# hail.net
KiCad netlist of a schematic drawn in EAGLE
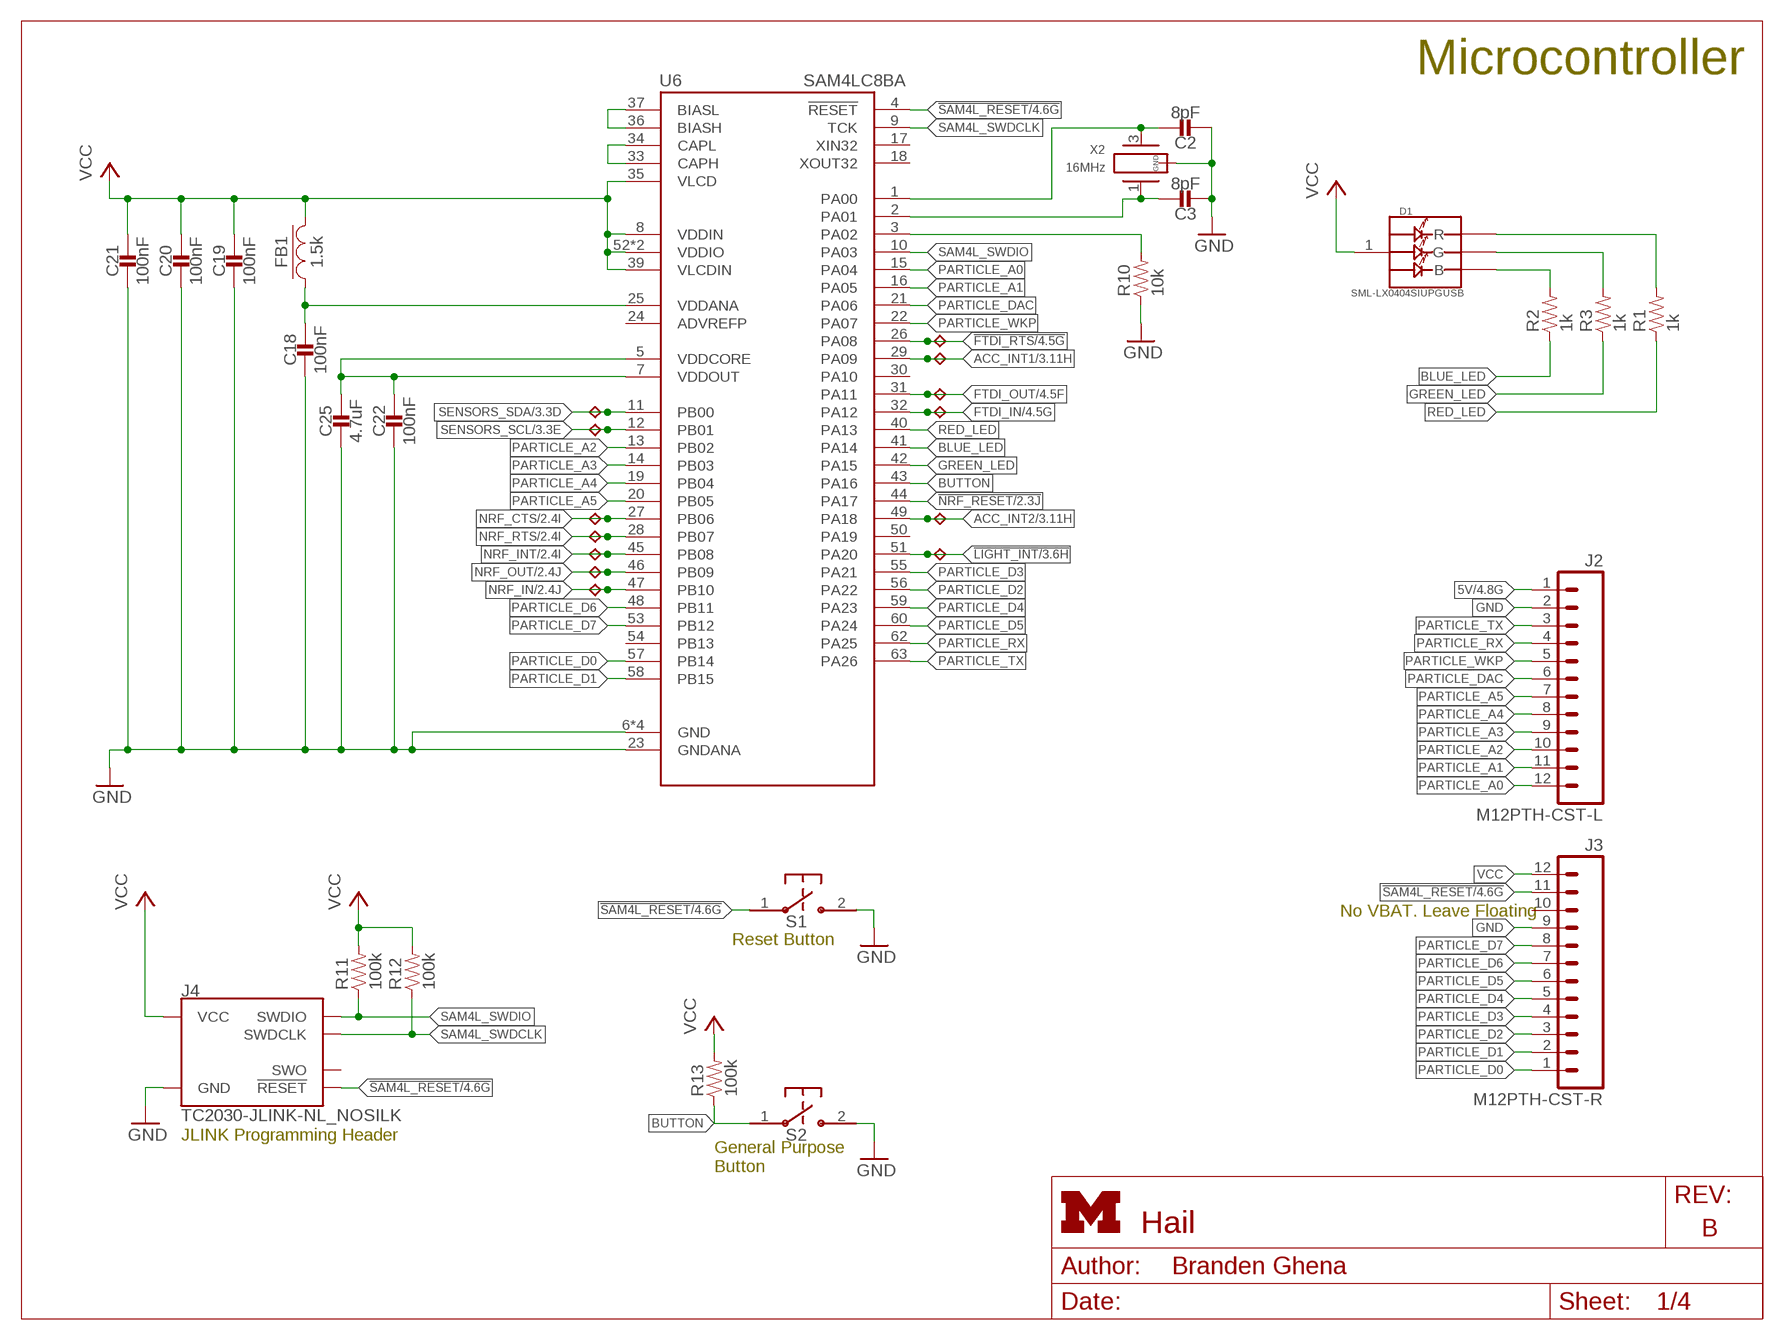
[diagram p0: schematic, sheet 1]
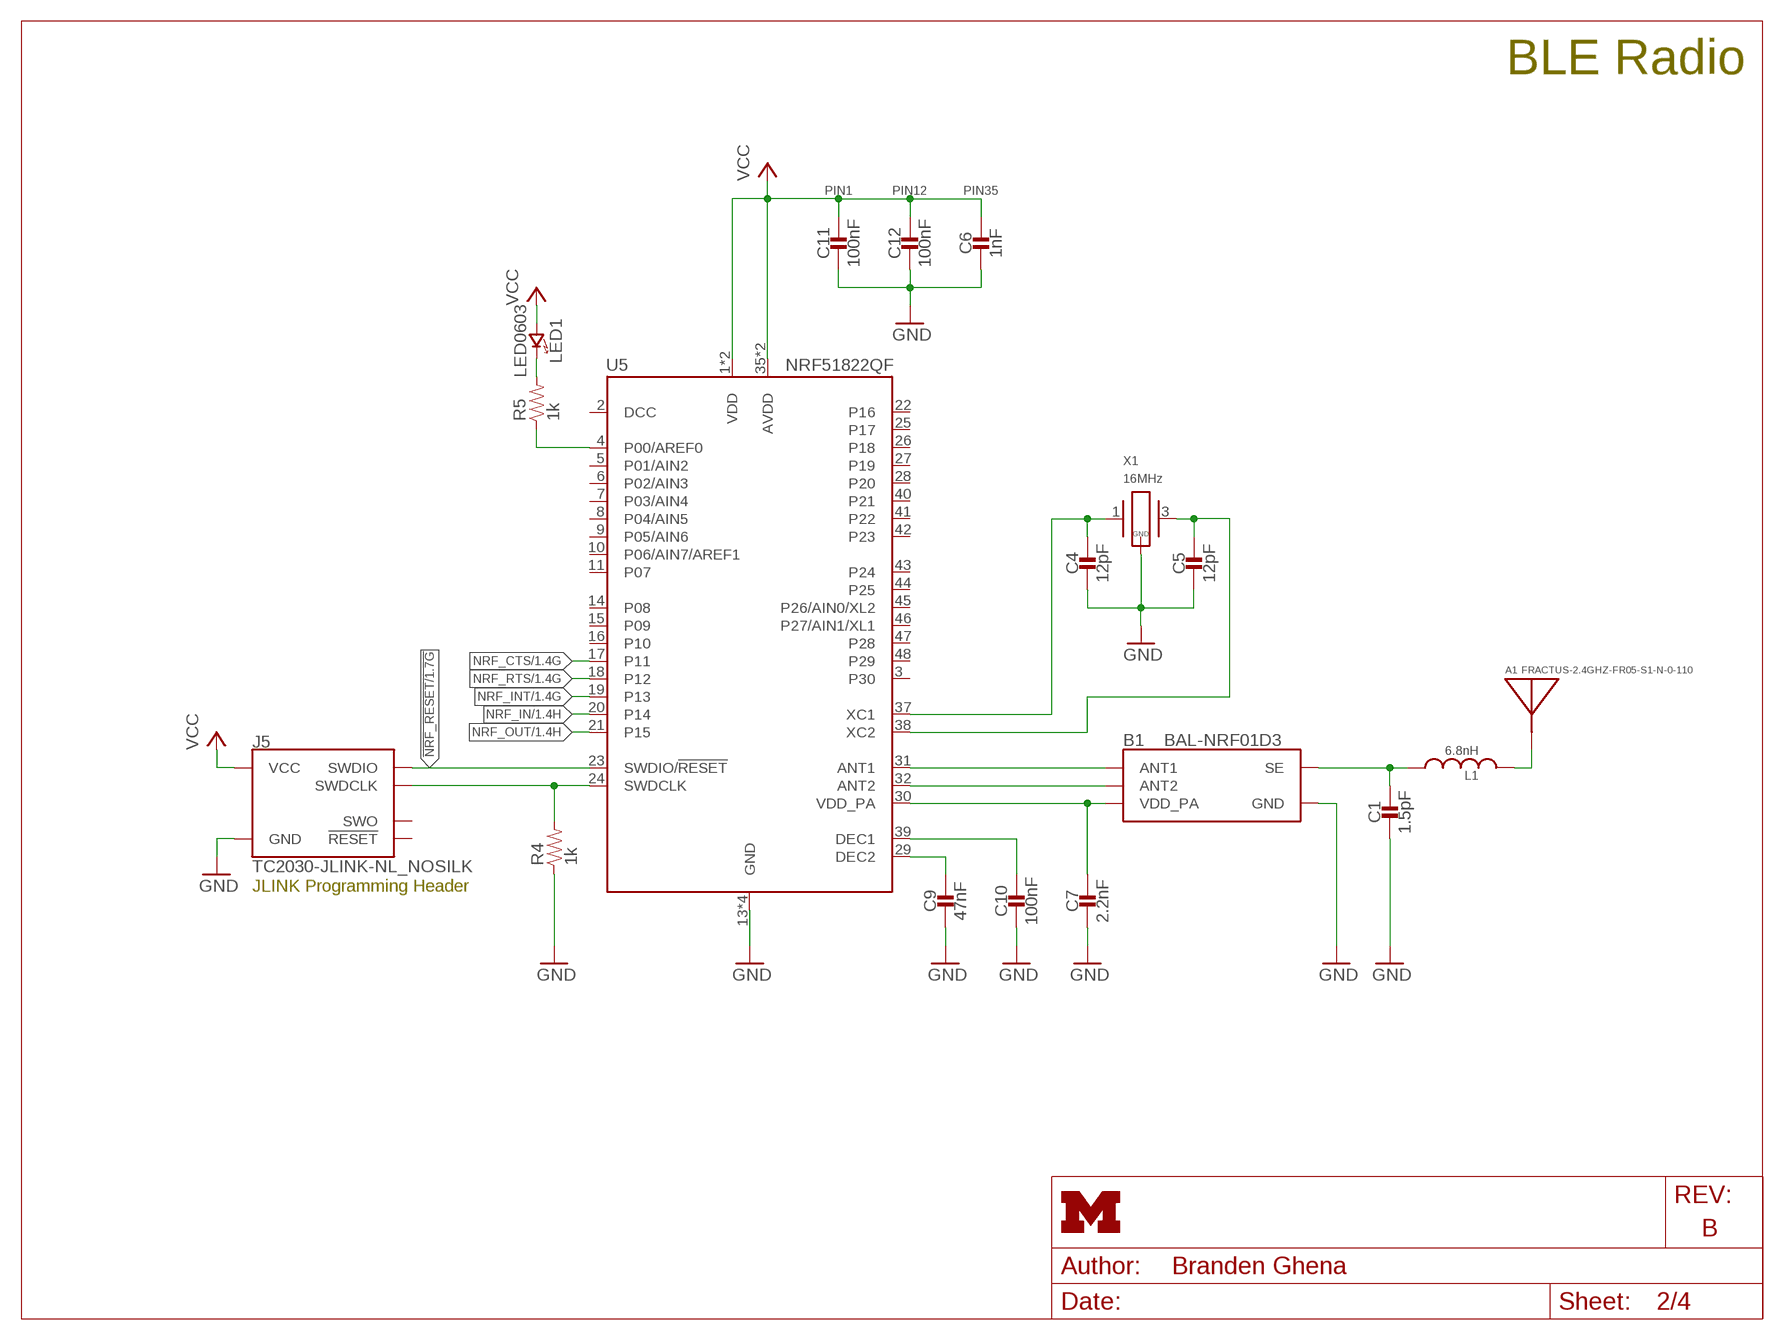
[diagram p1: schematic, sheet 2]
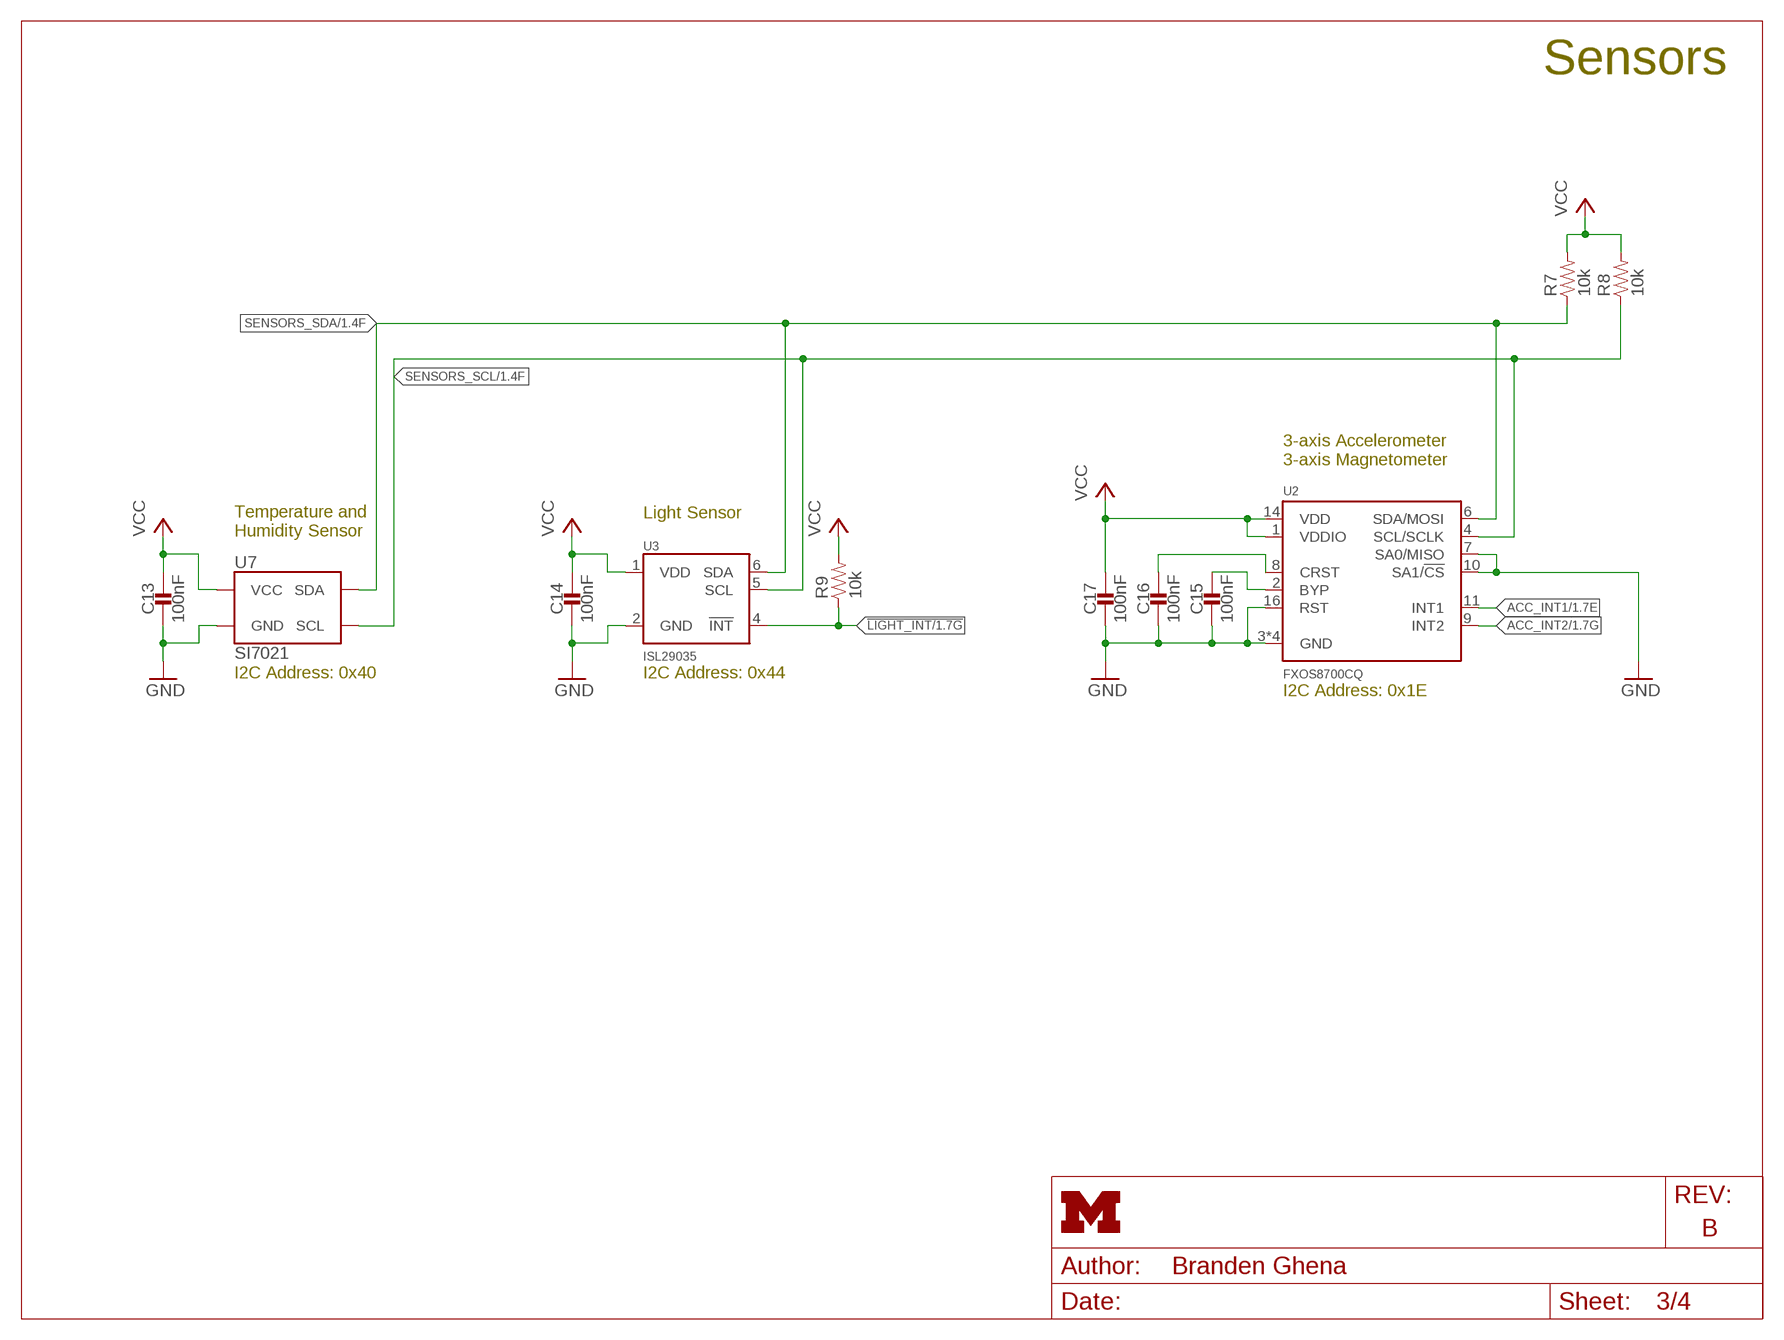
[diagram p2: schematic, sheet 3]
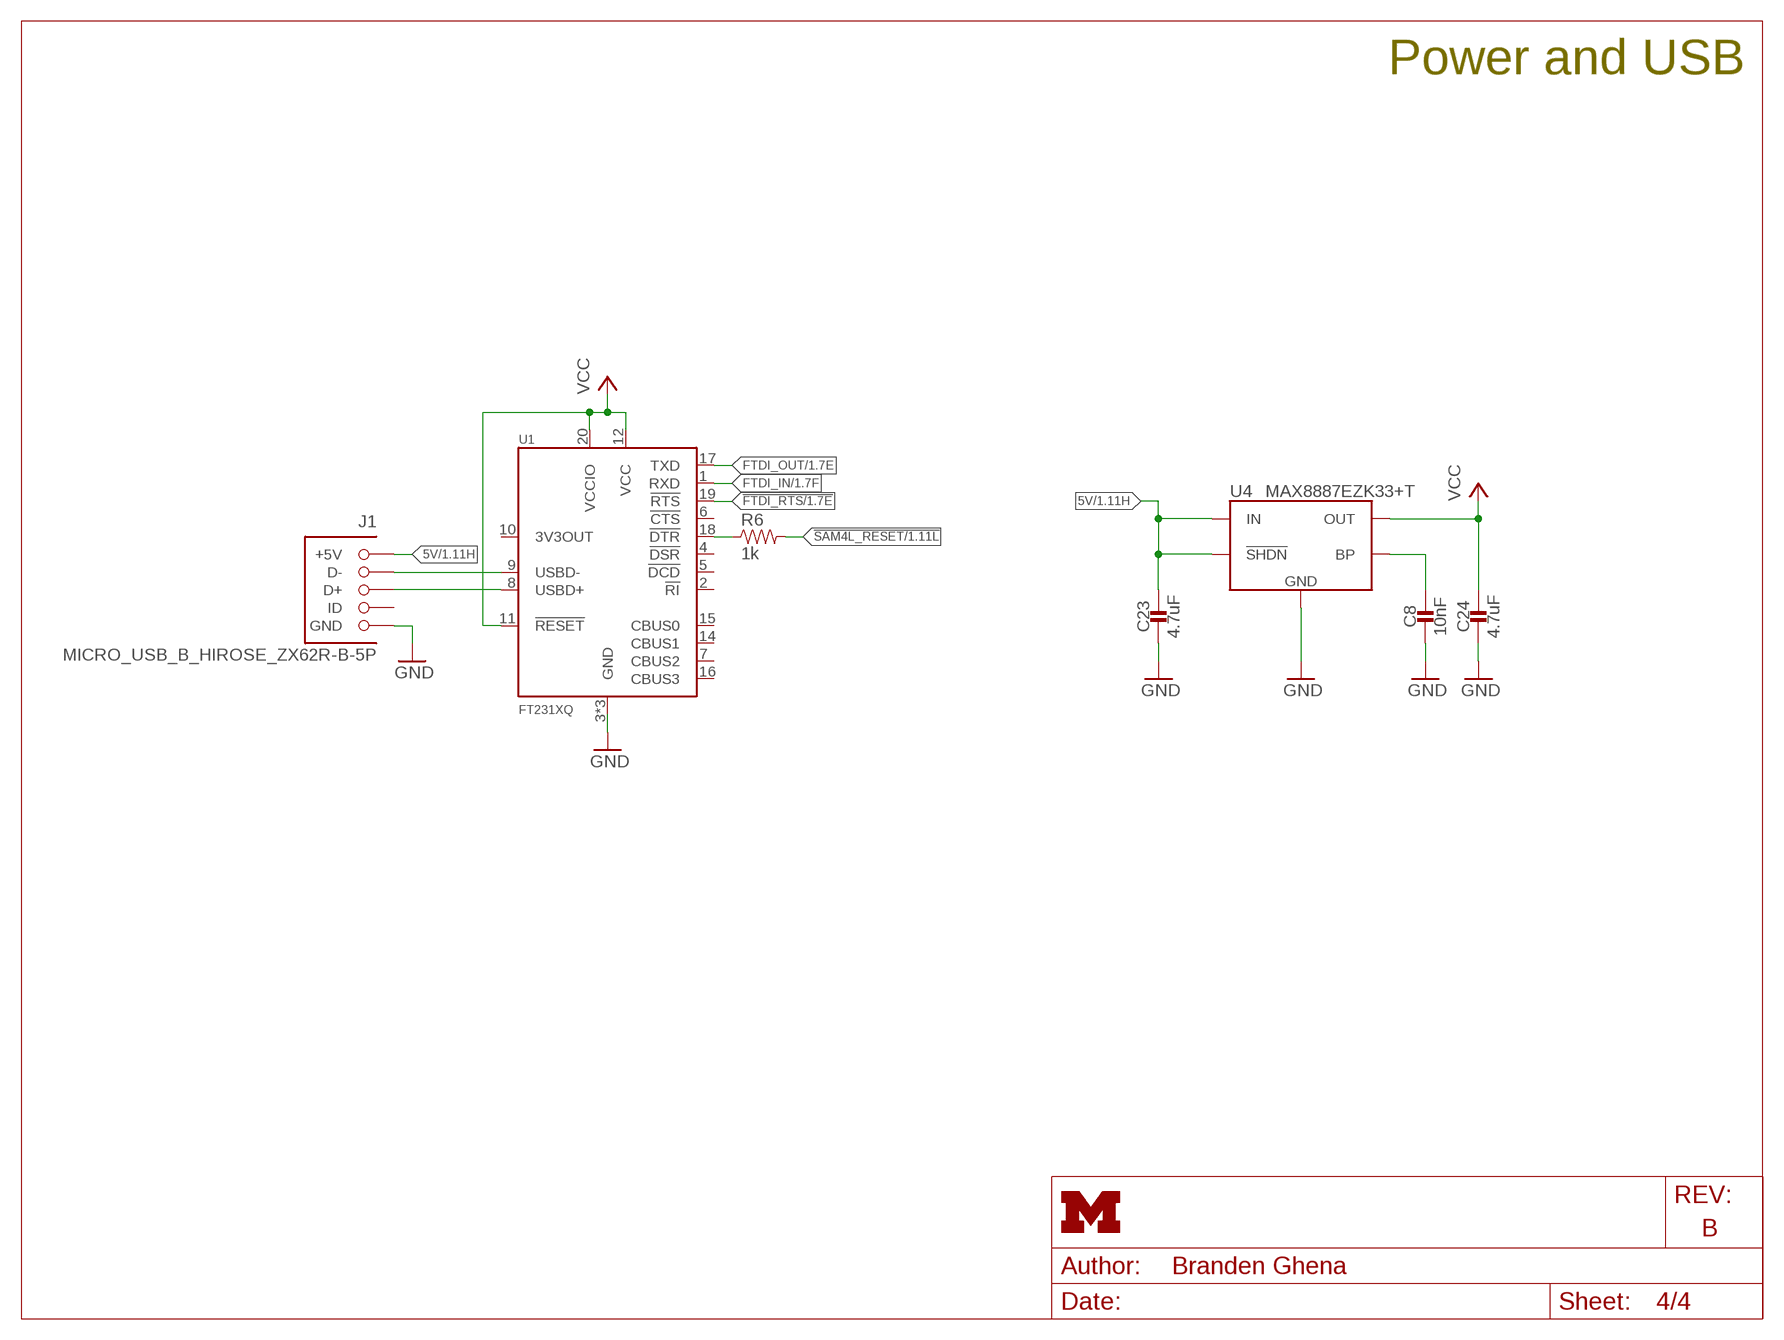
[diagram p3: schematic, sheet 4]

(export (version "E")
  (design (tool "Eeschema 10.0.6"))
  (components
    (comp (ref "C8")
      (value "10nF")
      (footprint "eagle-import:0402_CAP")
      (fields (field (name "MPN") "MF-CAP-0402-0.01uF"))
      (libsource (lib "eagle-import") (part "CAPACITOR0402_CAP"))
    )
    (comp (ref "C23")
      (value "4.7uF")
      (footprint "eagle-import:0402_CAP")
      (fields (field (name "MPN") "ZRB15XR61A475KE01D"))
      (libsource (lib "eagle-import") (part "CAPACITOR0402_CAP"))
    )
    (comp (ref "C24")
      (value "4.7uF")
      (footprint "eagle-import:0402_CAP")
      (fields (field (name "MPN") "ZRB15XR61A475KE01D"))
      (libsource (lib "eagle-import") (part "CAPACITOR0402_CAP"))
    )
    (comp (ref "J1")
      (value "MICRO_USB_B_HIROSE_ZX62R-B-5P")
      (footprint "eagle-import:USB_MICRO_B-HIROSE-ZX62R-B-5P")
      (fields (field (name "DIGIKEY") "H125274CT-ND") (field (name "MPN") "ZX62R-B-5P(30)"))
      (libsource (lib "eagle-import") (part "MICRO_USB_B_HIROSE_ZX62R-B-5P"))
    )
    (comp (ref "R6")
      (value "1k")
      (footprint "eagle-import:0402_RES")
      (fields (field (name "MPN") "MF-RES-0402-1K"))
      (libsource (lib "eagle-import") (part "RESISTOR0402_RES"))
    )
    (comp (ref "U1")
      (value "FT231XQ")
      (footprint "eagle-import:QFN-20-4MM")
      (fields (field (name "MPN") "FT231XQ-R"))
      (libsource (lib "eagle-import") (part "FT231XQ"))
    )
    (comp (ref "U4")
      (value "MAX8887EZK33+T")
      (footprint "eagle-import:SOT-23-5")
      (libsource (lib "eagle-import") (part "MAX8887EZK33+T"))
    )
    (comp (ref "A1")
      (value "FRACTUS-2.4GHZ-FR05-S1-N-0-110")
      (footprint "eagle-import:FRACTUS-ANTENNA-FR05-S1-N-0-110")
      (fields (field (name "MPN") "FR05-S1-N-0110B"))
      (libsource (lib "eagle-import") (part "FRACTUS-2.4GHZ-FR05-S1-N-0-110"))
    )
    (comp (ref "B1")
      (value "BAL-NRF01D3")
      (footprint "eagle-import:BAL-NRF01D3")
      (libsource (lib "eagle-import") (part "BAL-NRF01D3"))
    )
    (comp (ref "C1")
      (value "1.5pF")
      (footprint "eagle-import:0402_CAP")
      (fields (field (name "MPN") "GRM1555C1H1R5BA01D"))
      (libsource (lib "eagle-import") (part "CAPACITOR0402_CAP"))
    )
    (comp (ref "C4")
      (value "12pF")
      (footprint "eagle-import:0402_CAP")
      (fields (field (name "MPN") "GRM1555C1H120GA01D"))
      (libsource (lib "eagle-import") (part "CAPACITOR0402_CAP"))
    )
    (comp (ref "C5")
      (value "12pF")
      (footprint "eagle-import:0402_CAP")
      (fields (field (name "MPN") "GRM1555C1H120GA01D"))
      (libsource (lib "eagle-import") (part "CAPACITOR0402_CAP"))
    )
    (comp (ref "C6")
      (value "1nF")
      (footprint "eagle-import:0402_CAP")
      (fields (field (name "MPN") "MF-CAP-0402-1nF"))
      (libsource (lib "eagle-import") (part "CAPACITOR0402_CAP"))
    )
    (comp (ref "C7")
      (value "2.2nF")
      (footprint "eagle-import:0402_CAP")
      (fields (field (name "MPN") "GRM155R71E222KA01D"))
      (libsource (lib "eagle-import") (part "CAPACITOR0402_CAP"))
    )
    (comp (ref "C9")
      (value "47nF")
      (footprint "eagle-import:0402_CAP")
      (fields (field (name "MPN") "C1005X7R1C473K050BC"))
      (libsource (lib "eagle-import") (part "CAPACITOR0402_CAP"))
    )
    (comp (ref "C10")
      (value "100nF")
      (footprint "eagle-import:0402_CAP")
      (fields (field (name "MPN") "MF-CAP-0402-0.1uF"))
      (libsource (lib "eagle-import") (part "CAPACITOR0402_CAP"))
    )
    (comp (ref "C11")
      (value "100nF")
      (footprint "eagle-import:0402_CAP")
      (fields (field (name "MPN") "MF-CAP-0402-0.1uF"))
      (libsource (lib "eagle-import") (part "CAPACITOR0402_CAP"))
    )
    (comp (ref "C12")
      (value "100nF")
      (footprint "eagle-import:0402_CAP")
      (fields (field (name "MPN") "MF-CAP-0402-0.1uF"))
      (libsource (lib "eagle-import") (part "CAPACITOR0402_CAP"))
    )
    (comp (ref "J5")
      (value "TC2030-JLINK-NL_NOSILK")
      (footprint "eagle-import:TC2030-IDC-NL_NOSILK")
      (libsource (lib "eagle-import") (part "TC2030-JLINK-NL_NOSILK"))
    )
    (comp (ref "L1")
      (value "6.8nH")
      (footprint "eagle-import:0402_CAP")
      (fields (field (name "MPN") "LQW15AN6N8G00D"))
      (libsource (lib "eagle-import") (part "INDUCTOR0402"))
    )
    (comp (ref "LED1")
      (value "LED0603")
      (footprint "eagle-import:LED-0603")
      (fields (field (name "MPN") "MF-LED-0603-GREEN"))
      (libsource (lib "eagle-import") (part "LED0603"))
    )
    (comp (ref "R4")
      (value "1k")
      (footprint "eagle-import:0402_RES")
      (fields (field (name "MPN") "MF-RES-0402-1K"))
      (libsource (lib "eagle-import") (part "RESISTOR0402_RES"))
    )
    (comp (ref "R5")
      (value "1k")
      (footprint "eagle-import:0402_RES")
      (fields (field (name "MPN") "MF-RES-0402-1K"))
      (libsource (lib "eagle-import") (part "RESISTOR0402_RES"))
    )
    (comp (ref "U5")
      (value "NRF51822QF")
      (footprint "eagle-import:QFN-48-6MM")
      (fields (field (name "DIGIKEY") "1490-1049-1-ND") (field (name "MPN") "NRF51822-QFAC-R7"))
      (libsource (lib "eagle-import") (part "NRF51822QF"))
    )
    (comp (ref "X1")
      (value "16MHz")
      (footprint "eagle-import:TXC-8Y")
      (fields (field (name "MPN") "8Y-16.000MAAV-T"))
      (libsource (lib "eagle-import") (part "TXC-8Y"))
    )
    (comp (ref "C13")
      (value "100nF")
      (footprint "eagle-import:0402_CAP")
      (fields (field (name "MPN") "MF-CAP-0402-0.1uF"))
      (libsource (lib "eagle-import") (part "CAPACITOR0402_CAP"))
    )
    (comp (ref "C14")
      (value "100nF")
      (footprint "eagle-import:0402_CAP")
      (fields (field (name "MPN") "MF-CAP-0402-0.1uF"))
      (libsource (lib "eagle-import") (part "CAPACITOR0402_CAP"))
    )
    (comp (ref "C15")
      (value "100nF")
      (footprint "eagle-import:0402_CAP")
      (fields (field (name "MPN") "MF-CAP-0402-0.1uF"))
      (libsource (lib "eagle-import") (part "CAPACITOR0402_CAP"))
    )
    (comp (ref "C16")
      (value "100nF")
      (footprint "eagle-import:0402_CAP")
      (fields (field (name "MPN") "MF-CAP-0402-0.1uF"))
      (libsource (lib "eagle-import") (part "CAPACITOR0402_CAP"))
    )
    (comp (ref "C17")
      (value "100nF")
      (footprint "eagle-import:0402_CAP")
      (fields (field (name "MPN") "MF-CAP-0402-0.1uF"))
      (libsource (lib "eagle-import") (part "CAPACITOR0402_CAP"))
    )
    (comp (ref "R7")
      (value "10k")
      (footprint "eagle-import:0402_RES")
      (fields (field (name "MPN") "MF-RES-0402-10K"))
      (libsource (lib "eagle-import") (part "RESISTOR0402_RES"))
    )
    (comp (ref "R8")
      (value "10k")
      (footprint "eagle-import:0402_RES")
      (fields (field (name "MPN") "MF-RES-0402-10K"))
      (libsource (lib "eagle-import") (part "RESISTOR0402_RES"))
    )
    (comp (ref "R9")
      (value "10k")
      (footprint "eagle-import:0402_RES")
      (fields (field (name "MPN") "MF-RES-0402-10K"))
      (libsource (lib "eagle-import") (part "RESISTOR0402_RES"))
    )
    (comp (ref "U2")
      (value "FXOS8700CQ")
      (footprint "eagle-import:QFN-16-3MM")
      (fields (field (name "MPN") "FXOS8700CQR1"))
      (libsource (lib "eagle-import") (part "FXOS8700CQ"))
    )
    (comp (ref "U3")
      (value "ISL29035")
      (footprint "eagle-import:ODFN-6-1.5MMX1.6MM")
      (fields (field (name "MPN") "ISL29035IROZ-T7"))
      (libsource (lib "eagle-import") (part "ISL29035"))
    )
    (comp (ref "U7")
      (value "SI7021")
      (footprint "eagle-import:DFN-6_3MM")
      (fields (field (name "DIGIKEY") "336-3141-ND") (field (name "MPN") "SI7021-A20-GM1"))
      (libsource (lib "eagle-import") (part "SI7021"))
    )
    (comp (ref "C2")
      (value "8pF")
      (footprint "eagle-import:0402_CAP")
      (fields (field (name "MPN") "GRM1555C1H8R0BA01D"))
      (libsource (lib "eagle-import") (part "CAPACITOR0402_CAP"))
    )
    (comp (ref "C3")
      (value "8pF")
      (footprint "eagle-import:0402_CAP")
      (fields (field (name "MPN") "GRM1555C1H8R0BA01D"))
      (libsource (lib "eagle-import") (part "CAPACITOR0402_CAP"))
    )
    (comp (ref "C18")
      (value "100nF")
      (footprint "eagle-import:0402_CAP")
      (fields (field (name "MPN") "MF-CAP-0402-0.1uF"))
      (libsource (lib "eagle-import") (part "CAPACITOR0402_CAP"))
    )
    (comp (ref "C19")
      (value "100nF")
      (footprint "eagle-import:0402_CAP")
      (fields (field (name "MPN") "MF-CAP-0402-0.1uF"))
      (libsource (lib "eagle-import") (part "CAPACITOR0402_CAP"))
    )
    (comp (ref "C20")
      (value "100nF")
      (footprint "eagle-import:0402_CAP")
      (fields (field (name "MPN") "MF-CAP-0402-0.1uF"))
      (libsource (lib "eagle-import") (part "CAPACITOR0402_CAP"))
    )
    (comp (ref "C21")
      (value "100nF")
      (footprint "eagle-import:0402_CAP")
      (fields (field (name "MPN") "MF-CAP-0402-0.1uF"))
      (libsource (lib "eagle-import") (part "CAPACITOR0402_CAP"))
    )
    (comp (ref "C22")
      (value "100nF")
      (footprint "eagle-import:0402_CAP")
      (fields (field (name "MPN") "MF-CAP-0402-0.1uF"))
      (libsource (lib "eagle-import") (part "CAPACITOR0402_CAP"))
    )
    (comp (ref "C25")
      (value "4.7uF")
      (footprint "eagle-import:0402_CAP")
      (fields (field (name "MPN") "ZRB15XR61A475KE01D"))
      (libsource (lib "eagle-import") (part "CAPACITOR0402_CAP"))
    )
    (comp (ref "D1")
      (value "SML-LX0404SIUPGUSB")
      (footprint "eagle-import:1MM_SQ_4PAD")
      (libsource (lib "eagle-import") (part "SML-LX0404SIUPGUSB"))
    )
    (comp (ref "FB1")
      (value "1.5k")
      (footprint "eagle-import:0402_CAP")
      (fields (field (name "MPN") "CIM05J152NC"))
      (libsource (lib "eagle-import") (part "FERRITE_BEAD0402"))
    )
    (comp (ref "J2")
      (value "M12PTH-CST-L")
      (footprint "eagle-import:1X12-CASTELLATED")
      (fields (field (name "MPN") "MF-CON-2.54mm-01x12"))
      (libsource (lib "eagle-import") (part "M12PTH-CST-L"))
    )
    (comp (ref "J3")
      (value "M12PTH-CST-R")
      (footprint "eagle-import:1X12-CASTELLATED")
      (fields (field (name "MPN") "MF-CON-2.54mm-01x12"))
      (libsource (lib "eagle-import") (part "M12PTH-CST-R"))
    )
    (comp (ref "J4")
      (value "TC2030-JLINK-NL_NOSILK")
      (footprint "eagle-import:TC2030-IDC-NL_NOSILK")
      (libsource (lib "eagle-import") (part "TC2030-JLINK-NL_NOSILK"))
    )
    (comp (ref "R1")
      (value "1k")
      (footprint "eagle-import:0402_RES")
      (fields (field (name "MPN") "MF-RES-0402-1K"))
      (libsource (lib "eagle-import") (part "RESISTOR0402_RES"))
    )
    (comp (ref "R2")
      (value "1k")
      (footprint "eagle-import:0402_RES")
      (fields (field (name "MPN") "MF-RES-0402-1K"))
      (libsource (lib "eagle-import") (part "RESISTOR0402_RES"))
    )
    (comp (ref "R3")
      (value "1k")
      (footprint "eagle-import:0402_RES")
      (fields (field (name "MPN") "MF-RES-0402-1K"))
      (libsource (lib "eagle-import") (part "RESISTOR0402_RES"))
    )
    (comp (ref "R10")
      (value "10k")
      (footprint "eagle-import:0402_RES")
      (fields (field (name "MPN") "MF-RES-0402-10K"))
      (libsource (lib "eagle-import") (part "RESISTOR0402_RES"))
    )
    (comp (ref "R11")
      (value "100k")
      (footprint "eagle-import:0402_RES")
      (fields (field (name "MPN") "MF-RES-0402-100K"))
      (libsource (lib "eagle-import") (part "RESISTOR0402_RES"))
    )
    (comp (ref "R12")
      (value "100k")
      (footprint "eagle-import:0402_RES")
      (fields (field (name "MPN") "MF-RES-0402-100K"))
      (libsource (lib "eagle-import") (part "RESISTOR0402_RES"))
    )
    (comp (ref "R13")
      (value "100k")
      (footprint "eagle-import:0402_RES")
      (fields (field (name "MPN") "MF-RES-0402-100K"))
      (libsource (lib "eagle-import") (part "RESISTOR0402_RES"))
    )
    (comp (ref "S1")
      (value "B3U-1000P")
      (footprint "eagle-import:B3U-1000P")
      (libsource (lib "eagle-import") (part "B3U-1000P"))
    )
    (comp (ref "S2")
      (value "B3U-1000P")
      (footprint "eagle-import:B3U-1000P")
      (libsource (lib "eagle-import") (part "B3U-1000P"))
    )
    (comp (ref "TP1")
      (value "TPB1,27")
      (footprint "eagle-import:B1,27")
      (libsource (lib "eagle-import") (part "TPB1,27"))
    )
    (comp (ref "TP2")
      (value "TPB1,27")
      (footprint "eagle-import:B1,27")
      (libsource (lib "eagle-import") (part "TPB1,27"))
    )
    (comp (ref "TP3")
      (value "TPB1,27")
      (footprint "eagle-import:B1,27")
      (libsource (lib "eagle-import") (part "TPB1,27"))
    )
    (comp (ref "TP4")
      (value "TPB1,27")
      (footprint "eagle-import:B1,27")
      (libsource (lib "eagle-import") (part "TPB1,27"))
    )
    (comp (ref "TP5")
      (value "TPB1,27")
      (footprint "eagle-import:B1,27")
      (libsource (lib "eagle-import") (part "TPB1,27"))
    )
    (comp (ref "TP6")
      (value "TPB1,27")
      (footprint "eagle-import:B1,27")
      (libsource (lib "eagle-import") (part "TPB1,27"))
    )
    (comp (ref "TP7")
      (value "TPB1,27")
      (footprint "eagle-import:B1,27")
      (libsource (lib "eagle-import") (part "TPB1,27"))
    )
    (comp (ref "TP8")
      (value "TPB1,27")
      (footprint "eagle-import:B1,27")
      (libsource (lib "eagle-import") (part "TPB1,27"))
    )
    (comp (ref "TP9")
      (value "TPB1,27")
      (footprint "eagle-import:B1,27")
      (libsource (lib "eagle-import") (part "TPB1,27"))
    )
    (comp (ref "TP10")
      (value "TPB1,27")
      (footprint "eagle-import:B1,27")
      (libsource (lib "eagle-import") (part "TPB1,27"))
    )
    (comp (ref "TP11")
      (value "TPB1,27")
      (footprint "eagle-import:B1,27")
      (libsource (lib "eagle-import") (part "TPB1,27"))
    )
    (comp (ref "TP12")
      (value "TPB1,27")
      (footprint "eagle-import:B1,27")
      (libsource (lib "eagle-import") (part "TPB1,27"))
    )
    (comp (ref "TP13")
      (value "TPB1,27")
      (footprint "eagle-import:B1,27")
      (libsource (lib "eagle-import") (part "TPB1,27"))
    )
    (comp (ref "U6")
      (value "SAM4LC8BA")
      (footprint "eagle-import:QFN-64-9MM")
      (fields (field (name "DIGIKEY") "ATSAM4LC8BA-MURCT-ND") (field (name "MPN") "ATSAM4LC8BA-MU"))
      (libsource (lib "eagle-import") (part "SAM4LC8BA"))
    )
    (comp (ref "X2")
      (value "16MHz")
      (footprint "eagle-import:FHXXX")
      (fields (field (name "MPN") "FH1600015"))
      (libsource (lib "eagle-import") (part "FH1600015"))
    )
  )
  (nets
    (net (code "1") (name "5V") (class "Default")
      (node (ref "C23") (pin "1") (pinfunction "1_1") (pintype "bidirectional"))
      (node (ref "J1") (pin "1") (pinfunction "+5V_1") (pintype "bidirectional"))
      (node (ref "J2") (pin "1") (pinfunction "12_1") (pintype "passive"))
      (node (ref "U4") (pin "1") (pinfunction "IN_1") (pintype "bidirectional"))
      (node (ref "U4") (pin "3") (pinfunction "~{SHDN}_3") (pintype "bidirectional"))
    )
    (net (code "2") (name "ACC_INT1") (class "Default")
      (node (ref "TP8") (pin "TP") (pinfunction "TP_TP") (pintype "input"))
      (node (ref "U2") (pin "11") (pinfunction "INT1_11") (pintype "bidirectional"))
      (node (ref "U6") (pin "29") (pinfunction "PA09_29") (pintype "bidirectional"))
    )
    (net (code "3") (name "ACC_INT2") (class "Default")
      (node (ref "TP9") (pin "TP") (pinfunction "TP_TP") (pintype "input"))
      (node (ref "U2") (pin "9") (pinfunction "INT2_9") (pintype "bidirectional"))
      (node (ref "U6") (pin "49") (pinfunction "PA18_49") (pintype "bidirectional"))
    )
    (net (code "4") (name "ADVREFP") (class "Default")
      (node (ref "U6") (pin "24") (pinfunction "ADVREFP_24") (pintype "power_in"))
    )
    (net (code "5") (name "BLUE_LED") (class "Default")
      (node (ref "R2") (pin "1") (pinfunction "1_1") (pintype "passive"))
      (node (ref "U6") (pin "41") (pinfunction "PA14_41") (pintype "bidirectional"))
    )
    (net (code "6") (name "BUTTON") (class "Default")
      (node (ref "R13") (pin "1") (pinfunction "1_1") (pintype "passive"))
      (node (ref "S2") (pin "1") (pinfunction "P$1_1") (pintype "passive"))
      (node (ref "U6") (pin "43") (pinfunction "PA16_43") (pintype "bidirectional"))
    )
    (net (code "7") (name "FTDI_IN") (class "Default")
      (node (ref "TP13") (pin "TP") (pinfunction "TP_TP") (pintype "input"))
      (node (ref "U1") (pin "1") (pinfunction "RXD_1") (pintype "bidirectional"))
      (node (ref "U6") (pin "32") (pinfunction "PA12_32") (pintype "bidirectional"))
    )
    (net (code "8") (name "FTDI_OUT") (class "Default")
      (node (ref "TP12") (pin "TP") (pinfunction "TP_TP") (pintype "input"))
      (node (ref "U1") (pin "17") (pinfunction "TXD_17") (pintype "bidirectional"))
      (node (ref "U6") (pin "31") (pinfunction "PA11_31") (pintype "bidirectional"))
    )
    (net (code "9") (name "GND") (class "Default")
      (node (ref "B1") (pin "GND") (pinfunction "GND_GND") (pintype "bidirectional"))
      (node (ref "C1") (pin "2") (pinfunction "2_2") (pintype "bidirectional"))
      (node (ref "C10") (pin "2") (pinfunction "2_2") (pintype "bidirectional"))
      (node (ref "C11") (pin "2") (pinfunction "2_2") (pintype "bidirectional"))
      (node (ref "C12") (pin "2") (pinfunction "2_2") (pintype "bidirectional"))
      (node (ref "C13") (pin "2") (pinfunction "2_2") (pintype "bidirectional"))
      (node (ref "C14") (pin "2") (pinfunction "2_2") (pintype "bidirectional"))
      (node (ref "C15") (pin "2") (pinfunction "2_2") (pintype "bidirectional"))
      (node (ref "C16") (pin "2") (pinfunction "2_2") (pintype "bidirectional"))
      (node (ref "C17") (pin "2") (pinfunction "2_2") (pintype "bidirectional"))
      (node (ref "C18") (pin "2") (pinfunction "2_2") (pintype "bidirectional"))
      (node (ref "C19") (pin "2") (pinfunction "2_2") (pintype "bidirectional"))
      (node (ref "C2") (pin "2") (pinfunction "2_2") (pintype "bidirectional"))
      (node (ref "C20") (pin "2") (pinfunction "2_2") (pintype "bidirectional"))
      (node (ref "C21") (pin "2") (pinfunction "2_2") (pintype "bidirectional"))
      (node (ref "C22") (pin "2") (pinfunction "2_2") (pintype "bidirectional"))
      (node (ref "C23") (pin "2") (pinfunction "2_2") (pintype "bidirectional"))
      (node (ref "C24") (pin "2") (pinfunction "2_2") (pintype "bidirectional"))
      (node (ref "C25") (pin "2") (pinfunction "2_2") (pintype "bidirectional"))
      (node (ref "C3") (pin "2") (pinfunction "2_2") (pintype "bidirectional"))
      (node (ref "C4") (pin "2") (pinfunction "2_2") (pintype "bidirectional"))
      (node (ref "C5") (pin "2") (pinfunction "2_2") (pintype "bidirectional"))
      (node (ref "C6") (pin "2") (pinfunction "2_2") (pintype "bidirectional"))
      (node (ref "C7") (pin "2") (pinfunction "2_2") (pintype "bidirectional"))
      (node (ref "C8") (pin "2") (pinfunction "2_2") (pintype "bidirectional"))
      (node (ref "C9") (pin "2") (pinfunction "2_2") (pintype "bidirectional"))
      (node (ref "J1") (pin "5") (pinfunction "GND_5") (pintype "bidirectional"))
      (node (ref "J2") (pin "2") (pinfunction "11_2") (pintype "passive"))
      (node (ref "J3") (pin "9") (pinfunction "9_9") (pintype "passive"))
      (node (ref "J4") (pin "5") (pinfunction "GND_5") (pintype "bidirectional"))
      (node (ref "J5") (pin "5") (pinfunction "GND_5") (pintype "bidirectional"))
      (node (ref "R10") (pin "1") (pinfunction "1_1") (pintype "passive"))
      (node (ref "R4") (pin "1") (pinfunction "1_1") (pintype "passive"))
      (node (ref "S1") (pin "2") (pinfunction "P$2_2") (pintype "passive"))
      (node (ref "S2") (pin "2") (pinfunction "P$2_2") (pintype "passive"))
      (node (ref "U1") (pin "13") (pinfunction "GND_13") (pintype "bidirectional"))
      (node (ref "U1") (pin "3") (pinfunction "GND_3") (pintype "bidirectional"))
      (node (ref "U1") (pin "GND") (pinfunction "GND_GND") (pintype "bidirectional"))
      (node (ref "U2") (pin "10") (pinfunction "SA1/~{CS}_10") (pintype "bidirectional"))
      (node (ref "U2") (pin "12") (pinfunction "GND_12") (pintype "bidirectional"))
      (node (ref "U2") (pin "13") (pinfunction "GND_13") (pintype "bidirectional"))
      (node (ref "U2") (pin "16") (pinfunction "RST_16") (pintype "bidirectional"))
      (node (ref "U2") (pin "3") (pinfunction "GND_3") (pintype "bidirectional"))
      (node (ref "U2") (pin "5") (pinfunction "GND_5") (pintype "bidirectional"))
      (node (ref "U2") (pin "7") (pinfunction "SA0/MISO_7") (pintype "bidirectional"))
      (node (ref "U3") (pin "2") (pinfunction "GND_2") (pintype "bidirectional"))
      (node (ref "U4") (pin "2") (pinfunction "GND_2") (pintype "bidirectional"))
      (node (ref "U5") (pin "13") (pinfunction "GND_13") (pintype "bidirectional"))
      (node (ref "U5") (pin "33") (pinfunction "GND_33") (pintype "bidirectional"))
      (node (ref "U5") (pin "34") (pinfunction "GND_34") (pintype "bidirectional"))
      (node (ref "U5") (pin "GND") (pinfunction "GND_GND") (pintype "bidirectional"))
      (node (ref "U6") (pin "23") (pinfunction "GNDANA_23") (pintype "power_in"))
      (node (ref "U6") (pin "38") (pinfunction "GND_38") (pintype "power_in"))
      (node (ref "U6") (pin "6") (pinfunction "GND_6") (pintype "power_in"))
      (node (ref "U6") (pin "64") (pinfunction "GND_64") (pintype "power_in"))
      (node (ref "U6") (pin "GND") (pinfunction "GND_GND") (pintype "power_in"))
      (node (ref "U7") (pin "2") (pinfunction "GND_2") (pintype "bidirectional"))
      (node (ref "X1") (pin "2") (pinfunction "GND_2") (pintype "bidirectional"))
      (node (ref "X1") (pin "4") (pinfunction "GND_4") (pintype "bidirectional"))
      (node (ref "X2") (pin "2") (pinfunction "GND_2") (pintype "bidirectional"))
      (node (ref "X2") (pin "4") (pinfunction "GND_4") (pintype "bidirectional"))
    )
    (net (code "10") (name "GREEN_LED") (class "Default")
      (node (ref "R3") (pin "1") (pinfunction "1_1") (pintype "passive"))
      (node (ref "U6") (pin "42") (pinfunction "PA15_42") (pintype "bidirectional"))
    )
    (net (code "11") (name "NRF_CTS") (class "Default")
      (node (ref "TP1") (pin "TP") (pinfunction "TP_TP") (pintype "input"))
      (node (ref "U5") (pin "17") (pinfunction "P11_17") (pintype "bidirectional"))
      (node (ref "U6") (pin "27") (pinfunction "PB06_27") (pintype "bidirectional"))
    )
    (net (code "12") (name "NRF_IN") (class "Default")
      (node (ref "TP5") (pin "TP") (pinfunction "TP_TP") (pintype "input"))
      (node (ref "U5") (pin "20") (pinfunction "P14_20") (pintype "bidirectional"))
      (node (ref "U6") (pin "47") (pinfunction "PB10_47") (pintype "bidirectional"))
    )
    (net (code "13") (name "NRF_INT") (class "Default")
      (node (ref "TP3") (pin "TP") (pinfunction "TP_TP") (pintype "input"))
      (node (ref "U5") (pin "19") (pinfunction "P13_19") (pintype "bidirectional"))
      (node (ref "U6") (pin "45") (pinfunction "PB08_45") (pintype "bidirectional"))
    )
    (net (code "14") (name "NRF_OUT") (class "Default")
      (node (ref "TP4") (pin "TP") (pinfunction "TP_TP") (pintype "input"))
      (node (ref "U5") (pin "21") (pinfunction "P15_21") (pintype "bidirectional"))
      (node (ref "U6") (pin "46") (pinfunction "PB09_46") (pintype "bidirectional"))
    )
    (net (code "15") (name "NRF_RTS") (class "Default")
      (node (ref "TP2") (pin "TP") (pinfunction "TP_TP") (pintype "input"))
      (node (ref "U5") (pin "18") (pinfunction "P12_18") (pintype "bidirectional"))
      (node (ref "U6") (pin "28") (pinfunction "PB07_28") (pintype "bidirectional"))
    )
    (net (code "16") (name "Net-(A1-ANTENNA)") (class "Default")
      (node (ref "A1") (pin "ANT") (pinfunction "ANTENNA_ANT") (pintype "bidirectional"))
      (node (ref "L1") (pin "2") (pinfunction "2_2") (pintype "bidirectional"))
    )
    (net (code "17") (name "Net-(B1-PadSE)") (class "Default")
      (node (ref "B1") (pin "SE") (pinfunction "SE_SE") (pintype "bidirectional"))
      (node (ref "C1") (pin "1") (pinfunction "1_1") (pintype "bidirectional"))
      (node (ref "L1") (pin "1") (pinfunction "1_1") (pintype "bidirectional"))
    )
    (net (code "18") (name "Net-(B1-VDD_PA)") (class "Default")
      (node (ref "B1") (pin "VCC") (pinfunction "VDD_PA_VCC") (pintype "bidirectional"))
      (node (ref "C7") (pin "1") (pinfunction "1_1") (pintype "bidirectional"))
      (node (ref "U5") (pin "30") (pinfunction "VDD_PA_30") (pintype "bidirectional"))
    )
    (net (code "19") (name "Net-(D1-B)") (class "Default")
      (node (ref "D1") (pin "3") (pinfunction "B_3") (pintype "output"))
      (node (ref "R2") (pin "2") (pinfunction "2_2") (pintype "passive"))
    )
    (net (code "20") (name "Net-(D1-G)") (class "Default")
      (node (ref "D1") (pin "4") (pinfunction "G_4") (pintype "output"))
      (node (ref "R3") (pin "2") (pinfunction "2_2") (pintype "passive"))
    )
    (net (code "21") (name "Net-(D1-R)") (class "Default")
      (node (ref "D1") (pin "2") (pinfunction "R_2") (pintype "output"))
      (node (ref "R1") (pin "2") (pinfunction "2_2") (pintype "passive"))
    )
    (net (code "22") (name "Net-(FB1-P$1)") (class "Default")
      (node (ref "C18") (pin "1") (pinfunction "1_1") (pintype "bidirectional"))
      (node (ref "FB1") (pin "1") (pinfunction "P$1_1") (pintype "bidirectional"))
      (node (ref "U6") (pin "25") (pinfunction "VDDANA_25") (pintype "power_in"))
    )
    (net (code "23") (name "Net-(J1-D+)") (class "Default")
      (node (ref "J1") (pin "3") (pinfunction "D+_3") (pintype "bidirectional"))
      (node (ref "U1") (pin "8") (pinfunction "USBD+_8") (pintype "bidirectional"))
    )
    (net (code "24") (name "Net-(J1-D-)") (class "Default")
      (node (ref "J1") (pin "2") (pinfunction "D-_2") (pintype "bidirectional"))
      (node (ref "U1") (pin "9") (pinfunction "USBD-_9") (pintype "bidirectional"))
    )
    (net (code "25") (name "Net-(J5-SWDCLK)") (class "Default")
      (node (ref "J5") (pin "4") (pinfunction "SWDCLK_4") (pintype "bidirectional"))
      (node (ref "R4") (pin "2") (pinfunction "2_2") (pintype "passive"))
      (node (ref "U5") (pin "24") (pinfunction "SWDCLK_24") (pintype "bidirectional"))
    )
    (net (code "26") (name "Net-(LED1-CATHODE)") (class "Default")
      (node (ref "LED1") (pin "C") (pinfunction "CATHODE_C") (pintype "bidirectional"))
      (node (ref "R5") (pin "2") (pinfunction "2_2") (pintype "passive"))
    )
    (net (code "27") (name "Net-(U1-~{DTR})") (class "Default")
      (node (ref "R6") (pin "1") (pinfunction "1_1") (pintype "passive"))
      (node (ref "U1") (pin "18") (pinfunction "~{DTR}_18") (pintype "bidirectional"))
    )
    (net (code "28") (name "Net-(U2-BYP)") (class "Default")
      (node (ref "C15") (pin "1") (pinfunction "1_1") (pintype "bidirectional"))
      (node (ref "U2") (pin "2") (pinfunction "BYP_2") (pintype "bidirectional"))
    )
    (net (code "29") (name "Net-(U2-CRST)") (class "Default")
      (node (ref "C16") (pin "1") (pinfunction "1_1") (pintype "bidirectional"))
      (node (ref "U2") (pin "8") (pinfunction "CRST_8") (pintype "bidirectional"))
    )
    (net (code "30") (name "Net-(U4-BP)") (class "Default")
      (node (ref "C8") (pin "1") (pinfunction "1_1") (pintype "bidirectional"))
      (node (ref "U4") (pin "4") (pinfunction "BP_4") (pintype "bidirectional"))
    )
    (net (code "31") (name "Net-(U5-ANT1)") (class "Default")
      (node (ref "B1") (pin "ANT1") (pinfunction "ANT1_ANT1") (pintype "bidirectional"))
      (node (ref "U5") (pin "31") (pinfunction "ANT1_31") (pintype "bidirectional"))
    )
    (net (code "32") (name "Net-(U5-ANT2)") (class "Default")
      (node (ref "B1") (pin "ANT2") (pinfunction "ANT2_ANT2") (pintype "bidirectional"))
      (node (ref "U5") (pin "32") (pinfunction "ANT2_32") (pintype "bidirectional"))
    )
    (net (code "33") (name "Net-(U5-DEC1)") (class "Default")
      (node (ref "C10") (pin "1") (pinfunction "1_1") (pintype "bidirectional"))
      (node (ref "U5") (pin "39") (pinfunction "DEC1_39") (pintype "bidirectional"))
    )
    (net (code "34") (name "Net-(U5-DEC2)") (class "Default")
      (node (ref "C9") (pin "1") (pinfunction "1_1") (pintype "bidirectional"))
      (node (ref "U5") (pin "29") (pinfunction "DEC2_29") (pintype "bidirectional"))
    )
    (net (code "35") (name "Net-(U5-P00{slash}AREF0)") (class "Default")
      (node (ref "R5") (pin "1") (pinfunction "1_1") (pintype "passive"))
      (node (ref "U5") (pin "4") (pinfunction "P00/AREF0_4") (pintype "bidirectional"))
    )
    (net (code "36") (name "Net-(U5-XC1)") (class "Default")
      (node (ref "C4") (pin "1") (pinfunction "1_1") (pintype "bidirectional"))
      (node (ref "U5") (pin "37") (pinfunction "XC1_37") (pintype "bidirectional"))
      (node (ref "X1") (pin "1") (pinfunction "1_1") (pintype "bidirectional"))
    )
    (net (code "37") (name "Net-(U5-XC2)") (class "Default")
      (node (ref "C5") (pin "1") (pinfunction "1_1") (pintype "bidirectional"))
      (node (ref "U5") (pin "38") (pinfunction "XC2_38") (pintype "bidirectional"))
      (node (ref "X1") (pin "3") (pinfunction "2_3") (pintype "bidirectional"))
    )
    (net (code "38") (name "Net-(U6-BIASH)") (class "Default")
      (node (ref "U6") (pin "36") (pinfunction "BIASH_36") (pintype "bidirectional"))
      (node (ref "U6") (pin "37") (pinfunction "BIASL_37") (pintype "bidirectional"))
    )
    (net (code "39") (name "Net-(U6-CAPH)") (class "Default")
      (node (ref "U6") (pin "33") (pinfunction "CAPH_33") (pintype "bidirectional"))
      (node (ref "U6") (pin "34") (pinfunction "CAPL_34") (pintype "bidirectional"))
    )
    (net (code "40") (name "Net-(U6-PA00)") (class "Default")
      (node (ref "C2") (pin "1") (pinfunction "1_1") (pintype "bidirectional"))
      (node (ref "U6") (pin "1") (pinfunction "PA00_1") (pintype "bidirectional"))
      (node (ref "X2") (pin "3") (pinfunction "2_3") (pintype "bidirectional"))
    )
    (net (code "41") (name "Net-(U6-PA01)") (class "Default")
      (node (ref "C3") (pin "1") (pinfunction "1_1") (pintype "bidirectional"))
      (node (ref "U6") (pin "2") (pinfunction "PA01_2") (pintype "bidirectional"))
      (node (ref "X2") (pin "1") (pinfunction "1_1") (pintype "bidirectional"))
    )
    (net (code "42") (name "Net-(U6-PA02)") (class "Default")
      (node (ref "R10") (pin "2") (pinfunction "2_2") (pintype "passive"))
      (node (ref "U6") (pin "3") (pinfunction "PA02_3") (pintype "bidirectional"))
    )
    (net (code "43") (name "Net-(U6-VDDCORE)") (class "Default")
      (node (ref "C22") (pin "1") (pinfunction "1_1") (pintype "bidirectional"))
      (node (ref "C25") (pin "1") (pinfunction "1_1") (pintype "bidirectional"))
      (node (ref "U6") (pin "5") (pinfunction "VDDCORE_5") (pintype "power_in"))
      (node (ref "U6") (pin "7") (pinfunction "VDDOUT_7") (pintype "power_in"))
    )
    (net (code "44") (name "PARTICLE_A0") (class "Default")
      (node (ref "J2") (pin "12") (pinfunction "1_12") (pintype "passive"))
      (node (ref "U6") (pin "15") (pinfunction "PA04_15") (pintype "bidirectional"))
    )
    (net (code "45") (name "PARTICLE_A1") (class "Default")
      (node (ref "J2") (pin "11") (pinfunction "2_11") (pintype "passive"))
      (node (ref "U6") (pin "16") (pinfunction "PA05_16") (pintype "bidirectional"))
    )
    (net (code "46") (name "PARTICLE_A2") (class "Default")
      (node (ref "J2") (pin "10") (pinfunction "3_10") (pintype "passive"))
      (node (ref "U6") (pin "13") (pinfunction "PB02_13") (pintype "bidirectional"))
    )
    (net (code "47") (name "PARTICLE_A3") (class "Default")
      (node (ref "J2") (pin "9") (pinfunction "4_9") (pintype "passive"))
      (node (ref "U6") (pin "14") (pinfunction "PB03_14") (pintype "bidirectional"))
    )
    (net (code "48") (name "PARTICLE_A4") (class "Default")
      (node (ref "J2") (pin "8") (pinfunction "5_8") (pintype "passive"))
      (node (ref "U6") (pin "19") (pinfunction "PB04_19") (pintype "bidirectional"))
    )
    (net (code "49") (name "PARTICLE_A5") (class "Default")
      (node (ref "J2") (pin "7") (pinfunction "6_7") (pintype "passive"))
      (node (ref "U6") (pin "20") (pinfunction "PB05_20") (pintype "bidirectional"))
    )
    (net (code "50") (name "PARTICLE_D0") (class "Default")
      (node (ref "J3") (pin "1") (pinfunction "1_1") (pintype "passive"))
      (node (ref "U6") (pin "57") (pinfunction "PB14_57") (pintype "bidirectional"))
    )
    (net (code "51") (name "PARTICLE_D1") (class "Default")
      (node (ref "J3") (pin "2") (pinfunction "2_2") (pintype "passive"))
      (node (ref "U6") (pin "58") (pinfunction "PB15_58") (pintype "bidirectional"))
    )
    (net (code "52") (name "PARTICLE_D2") (class "Default")
      (node (ref "J3") (pin "3") (pinfunction "3_3") (pintype "passive"))
      (node (ref "U6") (pin "56") (pinfunction "PA22_56") (pintype "bidirectional"))
    )
    (net (code "53") (name "PARTICLE_D3") (class "Default")
      (node (ref "J3") (pin "4") (pinfunction "4_4") (pintype "passive"))
      (node (ref "U6") (pin "55") (pinfunction "PA21_55") (pintype "bidirectional"))
    )
    (net (code "54") (name "PARTICLE_D4") (class "Default")
      (node (ref "J3") (pin "5") (pinfunction "5_5") (pintype "passive"))
      (node (ref "U6") (pin "59") (pinfunction "PA23_59") (pintype "bidirectional"))
    )
    (net (code "55") (name "PARTICLE_D5") (class "Default")
      (node (ref "J3") (pin "6") (pinfunction "6_6") (pintype "passive"))
      (node (ref "U6") (pin "60") (pinfunction "PA24_60") (pintype "bidirectional"))
    )
    (net (code "56") (name "PARTICLE_D6") (class "Default")
      (node (ref "J3") (pin "7") (pinfunction "7_7") (pintype "passive"))
      (node (ref "U6") (pin "48") (pinfunction "PB11_48") (pintype "bidirectional"))
    )
    (net (code "57") (name "PARTICLE_D7") (class "Default")
      (node (ref "J3") (pin "8") (pinfunction "8_8") (pintype "passive"))
      (node (ref "U6") (pin "53") (pinfunction "PB12_53") (pintype "bidirectional"))
    )
    (net (code "58") (name "PARTICLE_DAC") (class "Default")
      (node (ref "J2") (pin "6") (pinfunction "7_6") (pintype "passive"))
      (node (ref "U6") (pin "21") (pinfunction "PA06_21") (pintype "bidirectional"))
    )
    (net (code "59") (name "PARTICLE_RX") (class "Default")
      (node (ref "J2") (pin "4") (pinfunction "9_4") (pintype "passive"))
      (node (ref "U6") (pin "62") (pinfunction "PA25_62") (pintype "bidirectional"))
    )
    (net (code "60") (name "PARTICLE_TX") (class "Default")
      (node (ref "J2") (pin "3") (pinfunction "10_3") (pintype "passive"))
      (node (ref "U6") (pin "63") (pinfunction "PA26_63") (pintype "bidirectional"))
    )
    (net (code "61") (name "PARTICLE_WKP") (class "Default")
      (node (ref "J2") (pin "5") (pinfunction "8_5") (pintype "passive"))
      (node (ref "U6") (pin "22") (pinfunction "PA07_22") (pintype "bidirectional"))
    )
    (net (code "62") (name "RED_LED") (class "Default")
      (node (ref "R1") (pin "1") (pinfunction "1_1") (pintype "passive"))
      (node (ref "U6") (pin "40") (pinfunction "PA13_40") (pintype "bidirectional"))
    )
    (net (code "63") (name "SAM4L_SWDCLK") (class "Default")
      (node (ref "J4") (pin "4") (pinfunction "SWDCLK_4") (pintype "bidirectional"))
      (node (ref "R12") (pin "1") (pinfunction "1_1") (pintype "passive"))
      (node (ref "U6") (pin "9") (pinfunction "TCK_9") (pintype "bidirectional"))
    )
    (net (code "64") (name "SAM4L_SWDIO") (class "Default")
      (node (ref "J4") (pin "2") (pinfunction "SWDIO_2") (pintype "bidirectional"))
      (node (ref "R11") (pin "1") (pinfunction "1_1") (pintype "passive"))
      (node (ref "U6") (pin "10") (pinfunction "PA03_10") (pintype "bidirectional"))
    )
    (net (code "65") (name "SENSORS_SCL") (class "Default")
      (node (ref "R8") (pin "1") (pinfunction "1_1") (pintype "passive"))
      (node (ref "TP7") (pin "TP") (pinfunction "TP_TP") (pintype "input"))
      (node (ref "U2") (pin "4") (pinfunction "SCL/SCLK_4") (pintype "bidirectional"))
      (node (ref "U3") (pin "5") (pinfunction "SCL_5") (pintype "bidirectional"))
      (node (ref "U6") (pin "12") (pinfunction "PB01_12") (pintype "bidirectional"))
      (node (ref "U7") (pin "6") (pinfunction "SCL_6") (pintype "bidirectional"))
    )
    (net (code "66") (name "SENSORS_SDA") (class "Default")
      (node (ref "R7") (pin "1") (pinfunction "1_1") (pintype "passive"))
      (node (ref "TP6") (pin "TP") (pinfunction "TP_TP") (pintype "input"))
      (node (ref "U2") (pin "6") (pinfunction "SDA/MOSI_6") (pintype "bidirectional"))
      (node (ref "U3") (pin "6") (pinfunction "SDA_6") (pintype "bidirectional"))
      (node (ref "U6") (pin "11") (pinfunction "PB00_11") (pintype "bidirectional"))
      (node (ref "U7") (pin "1") (pinfunction "SDA_1") (pintype "bidirectional"))
    )
    (net (code "67") (name "VCC") (class "Default")
      (node (ref "C11") (pin "1") (pinfunction "1_1") (pintype "bidirectional"))
      (node (ref "C12") (pin "1") (pinfunction "1_1") (pintype "bidirectional"))
      (node (ref "C13") (pin "1") (pinfunction "1_1") (pintype "bidirectional"))
      (node (ref "C14") (pin "1") (pinfunction "1_1") (pintype "bidirectional"))
      (node (ref "C17") (pin "1") (pinfunction "1_1") (pintype "bidirectional"))
      (node (ref "C19") (pin "1") (pinfunction "1_1") (pintype "bidirectional"))
      (node (ref "C20") (pin "1") (pinfunction "1_1") (pintype "bidirectional"))
      (node (ref "C21") (pin "1") (pinfunction "1_1") (pintype "bidirectional"))
      (node (ref "C24") (pin "1") (pinfunction "1_1") (pintype "bidirectional"))
      (node (ref "C6") (pin "1") (pinfunction "1_1") (pintype "bidirectional"))
      (node (ref "D1") (pin "1") (pinfunction "VDD_1") (pintype "bidirectional"))
      (node (ref "FB1") (pin "2") (pinfunction "P$2_2") (pintype "bidirectional"))
      (node (ref "J3") (pin "12") (pinfunction "12_12") (pintype "passive"))
      (node (ref "J4") (pin "1") (pinfunction "VCC_1") (pintype "bidirectional"))
      (node (ref "J5") (pin "1") (pinfunction "VCC_1") (pintype "bidirectional"))
      (node (ref "LED1") (pin "A") (pinfunction "ANODE_A") (pintype "bidirectional"))
      (node (ref "R11") (pin "2") (pinfunction "2_2") (pintype "passive"))
      (node (ref "R12") (pin "2") (pinfunction "2_2") (pintype "passive"))
      (node (ref "R13") (pin "2") (pinfunction "2_2") (pintype "passive"))
      (node (ref "R7") (pin "2") (pinfunction "2_2") (pintype "passive"))
      (node (ref "R8") (pin "2") (pinfunction "2_2") (pintype "passive"))
      (node (ref "R9") (pin "2") (pinfunction "2_2") (pintype "passive"))
      (node (ref "U1") (pin "11") (pinfunction "~{RESET}_11") (pintype "bidirectional"))
      (node (ref "U1") (pin "12") (pinfunction "VCC_12") (pintype "bidirectional"))
      (node (ref "U1") (pin "20") (pinfunction "VCCIO_20") (pintype "bidirectional"))
      (node (ref "U2") (pin "1") (pinfunction "VDDIO_1") (pintype "bidirectional"))
      (node (ref "U2") (pin "14") (pinfunction "VDD_14") (pintype "bidirectional"))
      (node (ref "U3") (pin "1") (pinfunction "VDD_1") (pintype "bidirectional"))
      (node (ref "U4") (pin "5") (pinfunction "OUT_5") (pintype "bidirectional"))
      (node (ref "U5") (pin "1") (pinfunction "VDD_1") (pintype "bidirectional"))
      (node (ref "U5") (pin "12") (pinfunction "VDD_12") (pintype "bidirectional"))
      (node (ref "U5") (pin "35") (pinfunction "AVDD_35") (pintype "bidirectional"))
      (node (ref "U5") (pin "36") (pinfunction "AVDD_36") (pintype "bidirectional"))
      (node (ref "U6") (pin "35") (pinfunction "VLCD_35") (pintype "bidirectional"))
      (node (ref "U6") (pin "39") (pinfunction "VLCDIN_39") (pintype "power_in"))
      (node (ref "U6") (pin "52") (pinfunction "VDDIO_52") (pintype "power_in"))
      (node (ref "U6") (pin "61") (pinfunction "VDDIO_61") (pintype "power_in"))
      (node (ref "U6") (pin "8") (pinfunction "VDDIN_8") (pintype "power_in"))
      (node (ref "U7") (pin "5") (pinfunction "VCC_5") (pintype "bidirectional"))
    )
    (net (code "68") (name "unconnected-(J1-ID-Pad4)") (class "Default")
      (node (ref "J1") (pin "4") (pinfunction "ID_4") (pintype "bidirectional"))
    )
    (net (code "69") (name "unconnected-(J3-Pad10)") (class "Default")
      (node (ref "J3") (pin "10") (pinfunction "10_10") (pintype "passive"))
    )
    (net (code "70") (name "unconnected-(J4-SWO-Pad6)") (class "Default")
      (node (ref "J4") (pin "6") (pinfunction "SWO_6") (pintype "bidirectional"))
    )
    (net (code "71") (name "unconnected-(J5-SWO-Pad6)") (class "Default")
      (node (ref "J5") (pin "6") (pinfunction "SWO_6") (pintype "bidirectional"))
    )
    (net (code "72") (name "unconnected-(J5-~{RESET}-Pad3)") (class "Default")
      (node (ref "J5") (pin "3") (pinfunction "~{RESET}_3") (pintype "bidirectional"))
    )
    (net (code "73") (name "unconnected-(U1-3V3OUT-Pad10)") (class "Default")
      (node (ref "U1") (pin "10") (pinfunction "3V3OUT_10") (pintype "bidirectional"))
    )
    (net (code "74") (name "unconnected-(U1-CBUS0-Pad15)") (class "Default")
      (node (ref "U1") (pin "15") (pinfunction "CBUS0_15") (pintype "bidirectional"))
    )
    (net (code "75") (name "unconnected-(U1-CBUS1-Pad14)") (class "Default")
      (node (ref "U1") (pin "14") (pinfunction "CBUS1_14") (pintype "bidirectional"))
    )
    (net (code "76") (name "unconnected-(U1-CBUS2-Pad7)") (class "Default")
      (node (ref "U1") (pin "7") (pinfunction "CBUS2_7") (pintype "bidirectional"))
    )
    (net (code "77") (name "unconnected-(U1-CBUS3-Pad16)") (class "Default")
      (node (ref "U1") (pin "16") (pinfunction "CBUS3_16") (pintype "bidirectional"))
    )
    (net (code "78") (name "unconnected-(U1-~{CTS}-Pad6)") (class "Default")
      (node (ref "U1") (pin "6") (pinfunction "~{CTS}_6") (pintype "bidirectional"))
    )
    (net (code "79") (name "unconnected-(U1-~{DCD}-Pad5)") (class "Default")
      (node (ref "U1") (pin "5") (pinfunction "~{DCD}_5") (pintype "bidirectional"))
    )
    (net (code "80") (name "unconnected-(U1-~{DSR}-Pad4)") (class "Default")
      (node (ref "U1") (pin "4") (pinfunction "~{DSR}_4") (pintype "bidirectional"))
    )
    (net (code "81") (name "unconnected-(U1-~{RI}-Pad2)") (class "Default")
      (node (ref "U1") (pin "2") (pinfunction "~{RI}_2") (pintype "bidirectional"))
    )
    (net (code "82") (name "unconnected-(U5-DCC-Pad2)") (class "Default")
      (node (ref "U5") (pin "2") (pinfunction "DCC_2") (pintype "bidirectional"))
    )
    (net (code "83") (name "unconnected-(U5-P01{slash}AIN2-Pad5)") (class "Default")
      (node (ref "U5") (pin "5") (pinfunction "P01/AIN2_5") (pintype "bidirectional"))
    )
    (net (code "84") (name "unconnected-(U5-P02{slash}AIN3-Pad6)") (class "Default")
      (node (ref "U5") (pin "6") (pinfunction "P02/AIN3_6") (pintype "bidirectional"))
    )
    (net (code "85") (name "unconnected-(U5-P03{slash}AIN4-Pad7)") (class "Default")
      (node (ref "U5") (pin "7") (pinfunction "P03/AIN4_7") (pintype "bidirectional"))
    )
    (net (code "86") (name "unconnected-(U5-P04{slash}AIN5-Pad8)") (class "Default")
      (node (ref "U5") (pin "8") (pinfunction "P04/AIN5_8") (pintype "bidirectional"))
    )
    (net (code "87") (name "unconnected-(U5-P05{slash}AIN6-Pad9)") (class "Default")
      (node (ref "U5") (pin "9") (pinfunction "P05/AIN6_9") (pintype "bidirectional"))
    )
    (net (code "88") (name "unconnected-(U5-P06{slash}AIN7{slash}AREF1-Pad10)") (class "Default")
      (node (ref "U5") (pin "10") (pinfunction "P06/AIN7/AREF1_10") (pintype "bidirectional"))
    )
    (net (code "89") (name "unconnected-(U5-P07-Pad11)") (class "Default")
      (node (ref "U5") (pin "11") (pinfunction "P07_11") (pintype "bidirectional"))
    )
    (net (code "90") (name "unconnected-(U5-P08-Pad14)") (class "Default")
      (node (ref "U5") (pin "14") (pinfunction "P08_14") (pintype "bidirectional"))
    )
    (net (code "91") (name "unconnected-(U5-P09-Pad15)") (class "Default")
      (node (ref "U5") (pin "15") (pinfunction "P09_15") (pintype "bidirectional"))
    )
    (net (code "92") (name "unconnected-(U5-P10-Pad16)") (class "Default")
      (node (ref "U5") (pin "16") (pinfunction "P10_16") (pintype "bidirectional"))
    )
    (net (code "93") (name "unconnected-(U5-P16-Pad22)") (class "Default")
      (node (ref "U5") (pin "22") (pinfunction "P16_22") (pintype "bidirectional"))
    )
    (net (code "94") (name "unconnected-(U5-P17-Pad25)") (class "Default")
      (node (ref "U5") (pin "25") (pinfunction "P17_25") (pintype "bidirectional"))
    )
    (net (code "95") (name "unconnected-(U5-P18-Pad26)") (class "Default")
      (node (ref "U5") (pin "26") (pinfunction "P18_26") (pintype "bidirectional"))
    )
    (net (code "96") (name "unconnected-(U5-P19-Pad27)") (class "Default")
      (node (ref "U5") (pin "27") (pinfunction "P19_27") (pintype "bidirectional"))
    )
    (net (code "97") (name "unconnected-(U5-P20-Pad28)") (class "Default")
      (node (ref "U5") (pin "28") (pinfunction "P20_28") (pintype "bidirectional"))
    )
    (net (code "98") (name "unconnected-(U5-P21-Pad40)") (class "Default")
      (node (ref "U5") (pin "40") (pinfunction "P21_40") (pintype "bidirectional"))
    )
    (net (code "99") (name "unconnected-(U5-P22-Pad41)") (class "Default")
      (node (ref "U5") (pin "41") (pinfunction "P22_41") (pintype "bidirectional"))
    )
    (net (code "100") (name "unconnected-(U5-P23-Pad42)") (class "Default")
      (node (ref "U5") (pin "42") (pinfunction "P23_42") (pintype "bidirectional"))
    )
    (net (code "101") (name "unconnected-(U5-P24-Pad43)") (class "Default")
      (node (ref "U5") (pin "43") (pinfunction "P24_43") (pintype "bidirectional"))
    )
    (net (code "102") (name "unconnected-(U5-P25-Pad44)") (class "Default")
      (node (ref "U5") (pin "44") (pinfunction "P25_44") (pintype "bidirectional"))
    )
    (net (code "103") (name "unconnected-(U5-P26{slash}AIN0{slash}XL2-Pad45)") (class "Default")
      (node (ref "U5") (pin "45") (pinfunction "P26/AIN0/XL2_45") (pintype "bidirectional"))
    )
    (net (code "104") (name "unconnected-(U5-P27{slash}AIN1{slash}XL1-Pad46)") (class "Default")
      (node (ref "U5") (pin "46") (pinfunction "P27/AIN1/XL1_46") (pintype "bidirectional"))
    )
    (net (code "105") (name "unconnected-(U5-P28-Pad47)") (class "Default")
      (node (ref "U5") (pin "47") (pinfunction "P28_47") (pintype "bidirectional"))
    )
    (net (code "106") (name "unconnected-(U5-P29-Pad48)") (class "Default")
      (node (ref "U5") (pin "48") (pinfunction "P29_48") (pintype "bidirectional"))
    )
    (net (code "107") (name "unconnected-(U5-P30-Pad3)") (class "Default")
      (node (ref "U5") (pin "3") (pinfunction "P30_3") (pintype "bidirectional"))
    )
    (net (code "108") (name "unconnected-(U6-PA10-Pad30)") (class "Default")
      (node (ref "U6") (pin "30") (pinfunction "PA10_30") (pintype "bidirectional"))
    )
    (net (code "109") (name "unconnected-(U6-PA19-Pad50)") (class "Default")
      (node (ref "U6") (pin "50") (pinfunction "PA19_50") (pintype "bidirectional"))
    )
    (net (code "110") (name "unconnected-(U6-PB13-Pad54)") (class "Default")
      (node (ref "U6") (pin "54") (pinfunction "PB13_54") (pintype "bidirectional"))
    )
    (net (code "111") (name "unconnected-(U6-XIN32-Pad17)") (class "Default")
      (node (ref "U6") (pin "17") (pinfunction "XIN32_17") (pintype "bidirectional"))
    )
    (net (code "112") (name "unconnected-(U6-XOUT32-Pad18)") (class "Default")
      (node (ref "U6") (pin "18") (pinfunction "XOUT32_18") (pintype "bidirectional"))
    )
    (net (code "113") (name "~{FTDI_RTS}") (class "Default")
      (node (ref "TP11") (pin "TP") (pinfunction "TP_TP") (pintype "input"))
      (node (ref "U1") (pin "19") (pinfunction "~{RTS}_19") (pintype "bidirectional"))
      (node (ref "U6") (pin "26") (pinfunction "PA08_26") (pintype "bidirectional"))
    )
    (net (code "114") (name "~{LIGHT_INT}") (class "Default")
      (node (ref "R9") (pin "1") (pinfunction "1_1") (pintype "passive"))
      (node (ref "TP10") (pin "TP") (pinfunction "TP_TP") (pintype "input"))
      (node (ref "U3") (pin "4") (pinfunction "~{INT}_4") (pintype "bidirectional"))
      (node (ref "U6") (pin "51") (pinfunction "PA20_51") (pintype "bidirectional"))
    )
    (net (code "115") (name "~{NRF_RESET}") (class "Default")
      (node (ref "J5") (pin "2") (pinfunction "SWDIO_2") (pintype "bidirectional"))
      (node (ref "U5") (pin "23") (pinfunction "SWDIO/~{RESET}_23") (pintype "bidirectional"))
      (node (ref "U6") (pin "44") (pinfunction "PA17_44") (pintype "bidirectional"))
    )
    (net (code "116") (name "~{SAM4L_RESET}") (class "Default")
      (node (ref "J3") (pin "11") (pinfunction "11_11") (pintype "passive"))
      (node (ref "J4") (pin "3") (pinfunction "~{RESET}_3") (pintype "bidirectional"))
      (node (ref "R6") (pin "2") (pinfunction "2_2") (pintype "passive"))
      (node (ref "S1") (pin "1") (pinfunction "P$1_1") (pintype "passive"))
      (node (ref "U6") (pin "4") (pinfunction "~{RESET}_4") (pintype "bidirectional"))
    )
  )
)
